# 08-USBOTG.net
KiCad netlist of a schematic drawn in Altium Designer
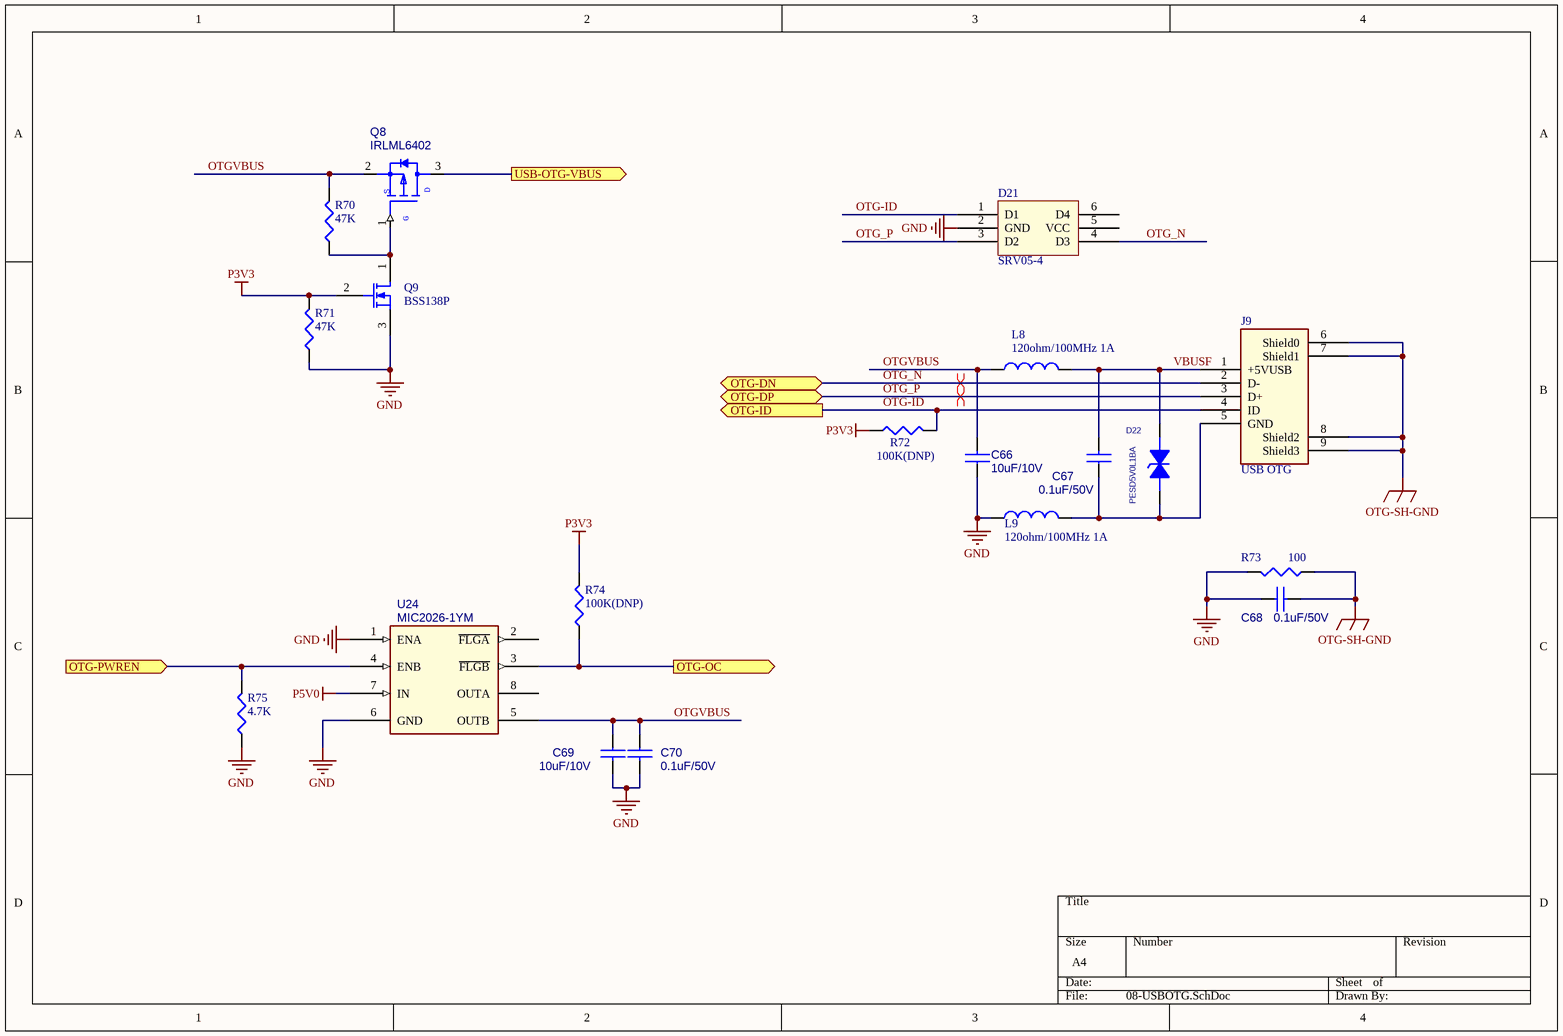
[diagram p0: 08-USBOTG.SchDoc]

(export (version "E")
  (design (tool "Eeschema 10.0.6"))
  (components
    (comp (ref "C66") (value "10uF/10V") (libsource (lib "*") (part "CAP_Dup1")))
    (comp (ref "C67") (value "0.1uF/50V") (libsource (lib "*") (part "CAP_Dup1")))
    (comp (ref "C68") (value "0.1uF/50V") (libsource (lib "*") (part "CAP_Dup1")))
    (comp (ref "C69") (value "10uF/10V") (libsource (lib "*") (part "CAP_Dup1")))
    (comp (ref "C70") (value "0.1uF/50V") (libsource (lib "*") (part "CAP_Dup1")))
    (comp (ref "D21") (value "SRV05-4") (footprint "SOT23-6") (libsource (lib "Schlib") (part "SRV05-4")))
    (comp (ref "D22") (value "PESD5V0L1BA") (libsource (lib "*") (part "PESD")))
    (comp (ref "J9")
      (value "USB OTG")
      (footprint "MINIUSB-TYPEAB")
      (fields (field (name "PART NUMBER") "SP063100800"))
      (libsource (lib "*") (part "FOX_UH51543-JS7"))
    )
    (comp (ref "L8")
      (value "120ohm/100MHz 1A")
      (footprint "0603")
      (description "Inductor")
      (fields (field (name "PUBLISHER") "Altium Limited"))
      (libsource (lib "Miscellaneous Devices") (part "Inductor"))
    )
    (comp (ref "L9")
      (value "120ohm/100MHz 1A")
      (footprint "0603")
      (description "Inductor")
      (fields (field (name "PUBLISHER") "Altium Limited"))
      (libsource (lib "Miscellaneous Devices") (part "Inductor"))
    )
    (comp (ref "Q8")
      (value "IRLML6402")
      (footprint "MOSFET")
      (fields (field (name "PART NUMBER") "SB934010010"))
      (libsource (lib "*") (part "AO3401L_SOT23-3_0"))
    )
    (comp (ref "Q9")
      (value "BSS138P")
      (footprint "NPN")
      (description "N-Channel MOSFET")
      (fields (field (name "PUBLISHER") "Altium Limited"))
      (libsource (lib "Miscellaneous Devices") (part "MOSFET-N"))
    )
    (comp (ref "R70") (value "47K") (footprint "0402") (libsource (lib "*") (part "CR16-1003FM")))
    (comp (ref "R71") (value "47K") (footprint "0402") (libsource (lib "*") (part "CR16-1003FM")))
    (comp (ref "R72") (value "100K(DNP)") (footprint "0402") (libsource (lib "*") (part "CR16-1003FM")))
    (comp (ref "R73") (value "100") (footprint "0402") (libsource (lib "*") (part "CR16-1003FM")))
    (comp (ref "R74") (value "100K(DNP)") (footprint "0402") (libsource (lib "*") (part "CR16-1003FM")))
    (comp (ref "R75") (value "4.7K") (footprint "0402") (libsource (lib "*") (part "CR16-1003FM")))
    (comp (ref "U24")
      (value "MIC2026-1YM")
      (footprint "SO8")
      (description "IC LIN SW PWR ACTIVE HIGH DUAL 2.7V-5.5V 0.5A SOIC8")
      (libsource (lib "*") (part "MIC2526_8P"))
    )
  )
  (nets
    (net (code "1") (name "/OTG-ID") (class "Default")
      (node (ref "D21") (pin "1") (pinfunction "D1_1") (pintype "passive"))
      (node (ref "J9") (pin "4") (pinfunction "ID_4") (pintype "passive"))
      (node (ref "R72") (pin "2") (pinfunction "2_2") (pintype "passive"))
    )
    (net (code "2") (name "/OTG-OC") (class "Default")
      (node (ref "R74") (pin "1") (pinfunction "1_1") (pintype "passive"))
      (node (ref "U24") (pin "3") (pinfunction "~{FLGB}_3") (pintype "output"))
    )
    (net (code "3") (name "/OTG-PWREN") (class "Default")
      (node (ref "R75") (pin "2") (pinfunction "2_2") (pintype "passive"))
      (node (ref "U24") (pin "4") (pinfunction "ENB_4") (pintype "input"))
    )
    (net (code "4") (name "/OTGVBUS") (class "Default")
      (node (ref "C66") (pin "2") (pinfunction "2_2") (pintype "passive"))
      (node (ref "C69") (pin "1") (pinfunction "1_1") (pintype "passive"))
      (node (ref "C70") (pin "1") (pinfunction "1_1") (pintype "passive"))
      (node (ref "L8") (pin "1") (pinfunction "1_1") (pintype "passive"))
      (node (ref "Q8") (pin "2") (pinfunction "S_2") (pintype "passive"))
      (node (ref "R70") (pin "2") (pinfunction "2_2") (pintype "passive"))
      (node (ref "U24") (pin "5") (pinfunction "OUTB_5") (pintype "power_in"))
    )
    (net (code "5") (name "/OTG_N") (class "Default")
      (node (ref "D21") (pin "4") (pinfunction "D3_4") (pintype "passive"))
      (node (ref "J9") (pin "2") (pinfunction "D-_2") (pintype "passive"))
    )
    (net (code "6") (name "/OTG_P") (class "Default")
      (node (ref "D21") (pin "3") (pinfunction "D2_3") (pintype "passive"))
      (node (ref "J9") (pin "3") (pinfunction "D+_3") (pintype "passive"))
    )
    (net (code "7") (name "/USB-OTG-VBUS") (class "Default")
      (node (ref "Q8") (pin "3") (pinfunction "D_3") (pintype "passive"))
    )
    (net (code "8") (name "/VBUSF") (class "Default")
      (node (ref "C67") (pin "2") (pinfunction "2_2") (pintype "passive"))
      (node (ref "D22") (pin "2") (pinfunction "2_2") (pintype "passive"))
      (node (ref "J9") (pin "1") (pinfunction "+5VUSB_1") (pintype "passive"))
      (node (ref "L8") (pin "2") (pinfunction "2_2") (pintype "passive"))
    )
    (net (code "9") (name "GND") (class "Default")
      (node (ref "C66") (pin "1") (pinfunction "1_1") (pintype "passive"))
      (node (ref "C68") (pin "1") (pinfunction "1_1") (pintype "passive"))
      (node (ref "C69") (pin "2") (pinfunction "2_2") (pintype "passive"))
      (node (ref "C70") (pin "2") (pinfunction "2_2") (pintype "passive"))
      (node (ref "D21") (pin "2") (pinfunction "GND_2") (pintype "passive"))
      (node (ref "L9") (pin "1") (pinfunction "1_1") (pintype "passive"))
      (node (ref "Q9") (pin "3") (pinfunction "S_3") (pintype "passive"))
      (node (ref "R71") (pin "1") (pinfunction "1_1") (pintype "passive"))
      (node (ref "R73") (pin "2") (pinfunction "2_2") (pintype "passive"))
      (node (ref "R75") (pin "1") (pinfunction "1_1") (pintype "passive"))
      (node (ref "U24") (pin "1") (pinfunction "ENA_1") (pintype "input"))
      (node (ref "U24") (pin "6") (pinfunction "GND_6") (pintype "power_in"))
    )
    (net (code "10") (name "Net-(J9-GND)") (class "Default")
      (node (ref "C67") (pin "1") (pinfunction "1_1") (pintype "passive"))
      (node (ref "D22") (pin "1") (pinfunction "1_1") (pintype "passive"))
      (node (ref "J9") (pin "5") (pinfunction "GND_5") (pintype "passive"))
      (node (ref "L9") (pin "2") (pinfunction "2_2") (pintype "passive"))
    )
    (net (code "11") (name "Net-(Q8-G)") (class "Default")
      (node (ref "Q8") (pin "1") (pinfunction "G_1") (pintype "input"))
      (node (ref "Q9") (pin "1") (pinfunction "D_1") (pintype "passive"))
      (node (ref "R70") (pin "1") (pinfunction "1_1") (pintype "passive"))
    )
    (net (code "12") (name "OTG-SH-GND") (class "Default")
      (node (ref "C68") (pin "2") (pinfunction "2_2") (pintype "passive"))
      (node (ref "J9") (pin "6") (pinfunction "Shield0_6") (pintype "passive"))
      (node (ref "J9") (pin "7") (pinfunction "Shield1_7") (pintype "passive"))
      (node (ref "J9") (pin "8") (pinfunction "Shield2_8") (pintype "passive"))
      (node (ref "J9") (pin "9") (pinfunction "Shield3_9") (pintype "passive"))
      (node (ref "R73") (pin "1") (pinfunction "1_1") (pintype "passive"))
    )
    (net (code "13") (name "P3V3") (class "Default")
      (node (ref "Q9") (pin "2") (pinfunction "G_2") (pintype "passive"))
      (node (ref "R71") (pin "2") (pinfunction "2_2") (pintype "passive"))
      (node (ref "R72") (pin "1") (pinfunction "1_1") (pintype "passive"))
      (node (ref "R74") (pin "2") (pinfunction "2_2") (pintype "passive"))
    )
    (net (code "14") (name "P5V0") (class "Default")
      (node (ref "U24") (pin "7") (pinfunction "IN_7") (pintype "input"))
    )
    (net (code "15") (name "unconnected-(D21-D4-Pad6)") (class "Default")
      (node (ref "D21") (pin "6") (pinfunction "D4_6") (pintype "passive"))
    )
    (net (code "16") (name "unconnected-(D21-VCC-Pad5)") (class "Default")
      (node (ref "D21") (pin "5") (pinfunction "VCC_5") (pintype "passive"))
    )
    (net (code "17") (name "unconnected-(U24-OUTA-Pad8)") (class "Default")
      (node (ref "U24") (pin "8") (pinfunction "OUTA_8") (pintype "power_in"))
    )
    (net (code "18") (name "unconnected-(U24-~{FLGA}-Pad2)") (class "Default")
      (node (ref "U24") (pin "2") (pinfunction "~{FLGA}_2") (pintype "output"))
    )
  )
)
